# SensorBreakout.net
KiCad netlist of a schematic drawn in Altium Designer
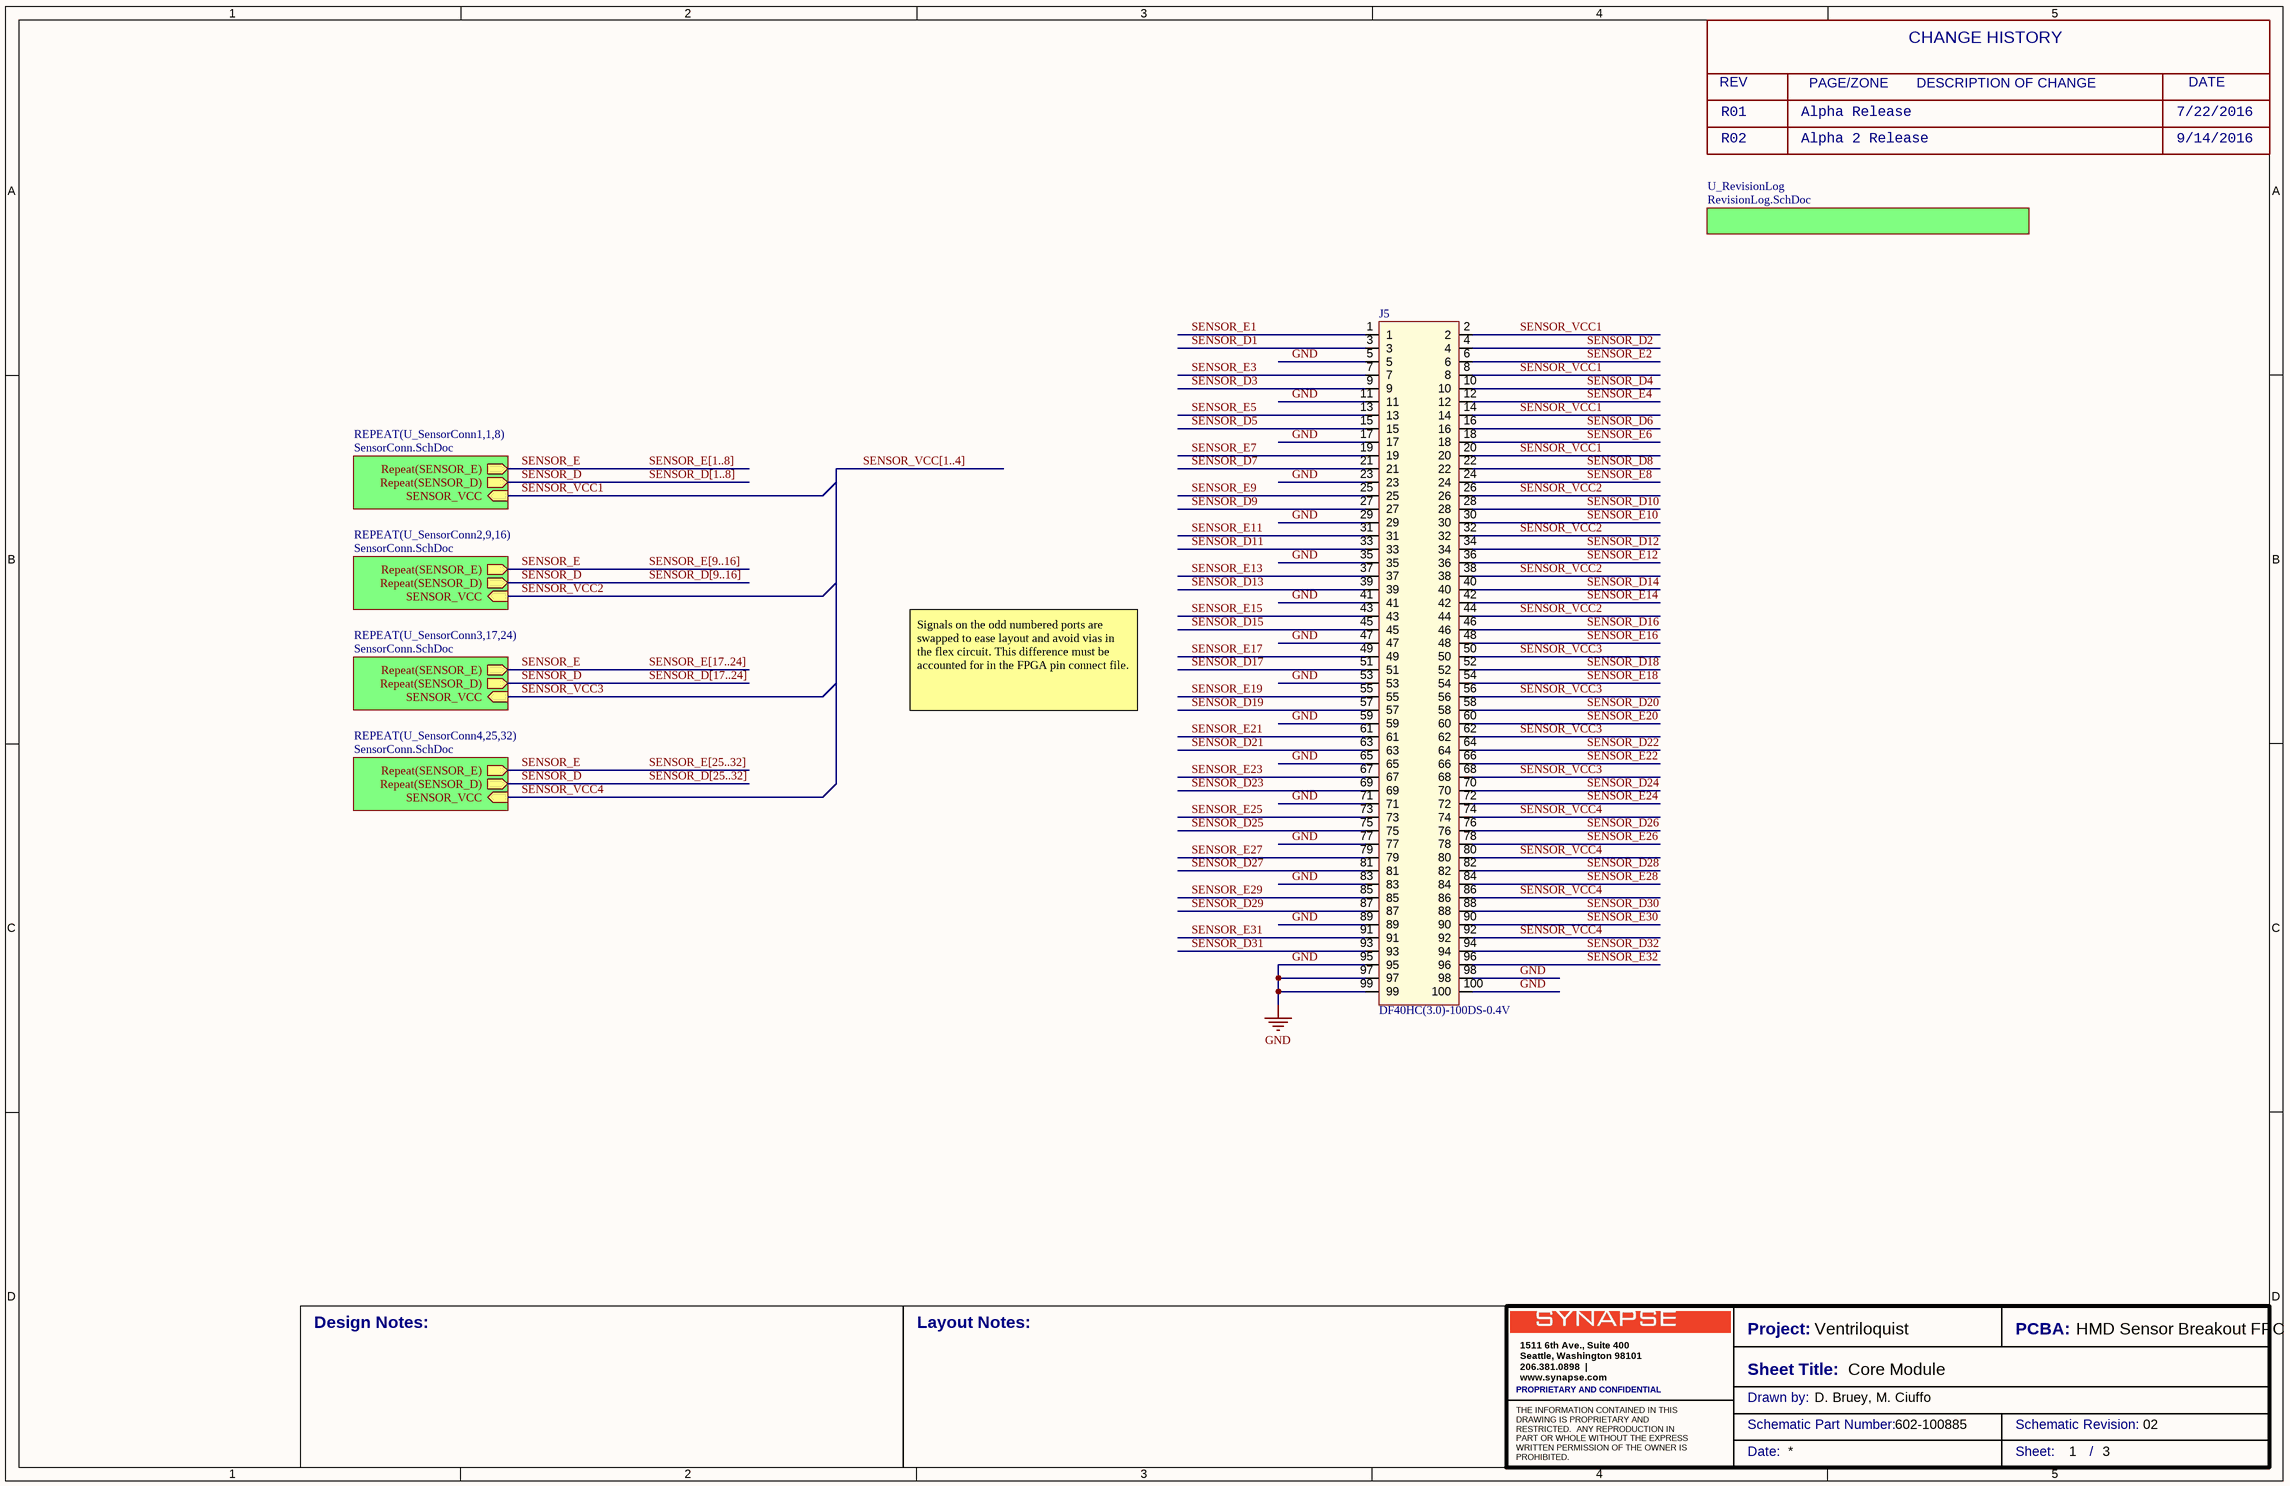
[diagram p0: SensorBreakout.SchDoc]

(export (version "E")
  (design (tool "Eeschema 10.0.6"))
  (components
    (comp (ref "J5")
      (value "DF40HC(3.0)-100DS-0.4V")
      (footprint "con100_hirose-df40c-100ds_129h")
      (description "CONN RCPT 100POS 0.4MM SMD GOLD 3.0MM")
      (fields (field (name "MFG") "Hirose") (field (name "VOLTAGE") "30V"))
      (libsource (lib "SynapseLibrary") (part "DF40C-100DS-0.4(51)"))
    )
  )
  (nets
    (net (code "2") (name "/SENSOR_D1") (class "Default")
      (node (ref "J5") (pin "3") (pinfunction "3_3") (pintype "passive"))
    )
    (net (code "3") (name "/SENSOR_D2") (class "Default")
      (node (ref "J5") (pin "4") (pinfunction "4_4") (pintype "passive"))
    )
    (net (code "4") (name "/SENSOR_D3") (class "Default")
      (node (ref "J5") (pin "9") (pinfunction "9_9") (pintype "passive"))
    )
    (net (code "5") (name "/SENSOR_D4") (class "Default")
      (node (ref "J5") (pin "10") (pinfunction "10_10") (pintype "passive"))
    )
    (net (code "6") (name "/SENSOR_D5") (class "Default")
      (node (ref "J5") (pin "15") (pinfunction "15_15") (pintype "passive"))
    )
    (net (code "7") (name "/SENSOR_D6") (class "Default")
      (node (ref "J5") (pin "16") (pinfunction "16_16") (pintype "passive"))
    )
    (net (code "8") (name "/SENSOR_D7") (class "Default")
      (node (ref "J5") (pin "21") (pinfunction "21_21") (pintype "passive"))
    )
    (net (code "9") (name "/SENSOR_D8") (class "Default")
      (node (ref "J5") (pin "22") (pinfunction "22_22") (pintype "passive"))
    )
    (net (code "10") (name "/SENSOR_D9") (class "Default")
      (node (ref "J5") (pin "27") (pinfunction "27_27") (pintype "passive"))
    )
    (net (code "11") (name "/SENSOR_D10") (class "Default")
      (node (ref "J5") (pin "28") (pinfunction "28_28") (pintype "passive"))
    )
    (net (code "12") (name "/SENSOR_D11") (class "Default")
      (node (ref "J5") (pin "33") (pinfunction "33_33") (pintype "passive"))
    )
    (net (code "13") (name "/SENSOR_D12") (class "Default")
      (node (ref "J5") (pin "34") (pinfunction "34_34") (pintype "passive"))
    )
    (net (code "14") (name "/SENSOR_D13") (class "Default")
      (node (ref "J5") (pin "39") (pinfunction "39_39") (pintype "passive"))
    )
    (net (code "15") (name "/SENSOR_D14") (class "Default")
      (node (ref "J5") (pin "40") (pinfunction "40_40") (pintype "passive"))
    )
    (net (code "16") (name "/SENSOR_D15") (class "Default")
      (node (ref "J5") (pin "45") (pinfunction "45_45") (pintype "passive"))
    )
    (net (code "17") (name "/SENSOR_D16") (class "Default")
      (node (ref "J5") (pin "46") (pinfunction "46_46") (pintype "passive"))
    )
    (net (code "18") (name "/SENSOR_D17") (class "Default")
      (node (ref "J5") (pin "51") (pinfunction "51_51") (pintype "passive"))
    )
    (net (code "19") (name "/SENSOR_D18") (class "Default")
      (node (ref "J5") (pin "52") (pinfunction "52_52") (pintype "passive"))
    )
    (net (code "20") (name "/SENSOR_D19") (class "Default")
      (node (ref "J5") (pin "57") (pinfunction "57_57") (pintype "passive"))
    )
    (net (code "21") (name "/SENSOR_D20") (class "Default")
      (node (ref "J5") (pin "58") (pinfunction "58_58") (pintype "passive"))
    )
    (net (code "22") (name "/SENSOR_D21") (class "Default")
      (node (ref "J5") (pin "63") (pinfunction "63_63") (pintype "passive"))
    )
    (net (code "23") (name "/SENSOR_D22") (class "Default")
      (node (ref "J5") (pin "64") (pinfunction "64_64") (pintype "passive"))
    )
    (net (code "24") (name "/SENSOR_D23") (class "Default")
      (node (ref "J5") (pin "69") (pinfunction "69_69") (pintype "passive"))
    )
    (net (code "25") (name "/SENSOR_D24") (class "Default")
      (node (ref "J5") (pin "70") (pinfunction "70_70") (pintype "passive"))
    )
    (net (code "26") (name "/SENSOR_D25") (class "Default")
      (node (ref "J5") (pin "75") (pinfunction "75_75") (pintype "passive"))
    )
    (net (code "27") (name "/SENSOR_D26") (class "Default")
      (node (ref "J5") (pin "76") (pinfunction "76_76") (pintype "passive"))
    )
    (net (code "28") (name "/SENSOR_D27") (class "Default")
      (node (ref "J5") (pin "81") (pinfunction "81_81") (pintype "passive"))
    )
    (net (code "29") (name "/SENSOR_D28") (class "Default")
      (node (ref "J5") (pin "82") (pinfunction "82_82") (pintype "passive"))
    )
    (net (code "30") (name "/SENSOR_D29") (class "Default")
      (node (ref "J5") (pin "87") (pinfunction "87_87") (pintype "passive"))
    )
    (net (code "31") (name "/SENSOR_D30") (class "Default")
      (node (ref "J5") (pin "88") (pinfunction "88_88") (pintype "passive"))
    )
    (net (code "32") (name "/SENSOR_D31") (class "Default")
      (node (ref "J5") (pin "93") (pinfunction "93_93") (pintype "passive"))
    )
    (net (code "33") (name "/SENSOR_D32") (class "Default")
      (node (ref "J5") (pin "94") (pinfunction "94_94") (pintype "passive"))
    )
    (net (code "39") (name "/SENSOR_E1") (class "Default")
      (node (ref "J5") (pin "1") (pinfunction "1_1") (pintype "passive"))
    )
    (net (code "40") (name "/SENSOR_E2") (class "Default")
      (node (ref "J5") (pin "6") (pinfunction "6_6") (pintype "passive"))
    )
    (net (code "41") (name "/SENSOR_E3") (class "Default")
      (node (ref "J5") (pin "7") (pinfunction "7_7") (pintype "passive"))
    )
    (net (code "42") (name "/SENSOR_E4") (class "Default")
      (node (ref "J5") (pin "12") (pinfunction "12_12") (pintype "passive"))
    )
    (net (code "43") (name "/SENSOR_E5") (class "Default")
      (node (ref "J5") (pin "13") (pinfunction "13_13") (pintype "passive"))
    )
    (net (code "44") (name "/SENSOR_E6") (class "Default")
      (node (ref "J5") (pin "18") (pinfunction "18_18") (pintype "passive"))
    )
    (net (code "45") (name "/SENSOR_E7") (class "Default")
      (node (ref "J5") (pin "19") (pinfunction "19_19") (pintype "passive"))
    )
    (net (code "46") (name "/SENSOR_E8") (class "Default")
      (node (ref "J5") (pin "24") (pinfunction "24_24") (pintype "passive"))
    )
    (net (code "47") (name "/SENSOR_E9") (class "Default")
      (node (ref "J5") (pin "25") (pinfunction "25_25") (pintype "passive"))
    )
    (net (code "48") (name "/SENSOR_E10") (class "Default")
      (node (ref "J5") (pin "30") (pinfunction "30_30") (pintype "passive"))
    )
    (net (code "49") (name "/SENSOR_E11") (class "Default")
      (node (ref "J5") (pin "31") (pinfunction "31_31") (pintype "passive"))
    )
    (net (code "50") (name "/SENSOR_E12") (class "Default")
      (node (ref "J5") (pin "36") (pinfunction "36_36") (pintype "passive"))
    )
    (net (code "51") (name "/SENSOR_E13") (class "Default")
      (node (ref "J5") (pin "37") (pinfunction "37_37") (pintype "passive"))
    )
    (net (code "52") (name "/SENSOR_E14") (class "Default")
      (node (ref "J5") (pin "42") (pinfunction "42_42") (pintype "passive"))
    )
    (net (code "53") (name "/SENSOR_E15") (class "Default")
      (node (ref "J5") (pin "43") (pinfunction "43_43") (pintype "passive"))
    )
    (net (code "54") (name "/SENSOR_E16") (class "Default")
      (node (ref "J5") (pin "48") (pinfunction "48_48") (pintype "passive"))
    )
    (net (code "55") (name "/SENSOR_E17") (class "Default")
      (node (ref "J5") (pin "49") (pinfunction "49_49") (pintype "passive"))
    )
    (net (code "56") (name "/SENSOR_E18") (class "Default")
      (node (ref "J5") (pin "54") (pinfunction "54_54") (pintype "passive"))
    )
    (net (code "57") (name "/SENSOR_E19") (class "Default")
      (node (ref "J5") (pin "55") (pinfunction "55_55") (pintype "passive"))
    )
    (net (code "58") (name "/SENSOR_E20") (class "Default")
      (node (ref "J5") (pin "60") (pinfunction "60_60") (pintype "passive"))
    )
    (net (code "59") (name "/SENSOR_E21") (class "Default")
      (node (ref "J5") (pin "61") (pinfunction "61_61") (pintype "passive"))
    )
    (net (code "60") (name "/SENSOR_E22") (class "Default")
      (node (ref "J5") (pin "66") (pinfunction "66_66") (pintype "passive"))
    )
    (net (code "61") (name "/SENSOR_E23") (class "Default")
      (node (ref "J5") (pin "67") (pinfunction "67_67") (pintype "passive"))
    )
    (net (code "62") (name "/SENSOR_E24") (class "Default")
      (node (ref "J5") (pin "72") (pinfunction "72_72") (pintype "passive"))
    )
    (net (code "63") (name "/SENSOR_E25") (class "Default")
      (node (ref "J5") (pin "73") (pinfunction "73_73") (pintype "passive"))
    )
    (net (code "64") (name "/SENSOR_E26") (class "Default")
      (node (ref "J5") (pin "78") (pinfunction "78_78") (pintype "passive"))
    )
    (net (code "65") (name "/SENSOR_E27") (class "Default")
      (node (ref "J5") (pin "79") (pinfunction "79_79") (pintype "passive"))
    )
    (net (code "66") (name "/SENSOR_E28") (class "Default")
      (node (ref "J5") (pin "84") (pinfunction "84_84") (pintype "passive"))
    )
    (net (code "67") (name "/SENSOR_E29") (class "Default")
      (node (ref "J5") (pin "85") (pinfunction "85_85") (pintype "passive"))
    )
    (net (code "68") (name "/SENSOR_E30") (class "Default")
      (node (ref "J5") (pin "90") (pinfunction "90_90") (pintype "passive"))
    )
    (net (code "69") (name "/SENSOR_E31") (class "Default")
      (node (ref "J5") (pin "91") (pinfunction "91_91") (pintype "passive"))
    )
    (net (code "70") (name "/SENSOR_E32") (class "Default")
      (node (ref "J5") (pin "96") (pinfunction "96_96") (pintype "passive"))
    )
    (net (code "75") (name "/SENSOR_VCC1") (class "Default")
      (node (ref "J5") (pin "14") (pinfunction "14_14") (pintype "passive"))
      (node (ref "J5") (pin "2") (pinfunction "2_2") (pintype "passive"))
      (node (ref "J5") (pin "20") (pinfunction "20_20") (pintype "passive"))
      (node (ref "J5") (pin "8") (pinfunction "8_8") (pintype "passive"))
    )
    (net (code "76") (name "/SENSOR_VCC2") (class "Default")
      (node (ref "J5") (pin "26") (pinfunction "26_26") (pintype "passive"))
      (node (ref "J5") (pin "32") (pinfunction "32_32") (pintype "passive"))
      (node (ref "J5") (pin "38") (pinfunction "38_38") (pintype "passive"))
      (node (ref "J5") (pin "44") (pinfunction "44_44") (pintype "passive"))
    )
    (net (code "77") (name "/SENSOR_VCC3") (class "Default")
      (node (ref "J5") (pin "50") (pinfunction "50_50") (pintype "passive"))
      (node (ref "J5") (pin "56") (pinfunction "56_56") (pintype "passive"))
      (node (ref "J5") (pin "62") (pinfunction "62_62") (pintype "passive"))
      (node (ref "J5") (pin "68") (pinfunction "68_68") (pintype "passive"))
    )
    (net (code "78") (name "/SENSOR_VCC4") (class "Default")
      (node (ref "J5") (pin "74") (pinfunction "74_74") (pintype "passive"))
      (node (ref "J5") (pin "80") (pinfunction "80_80") (pintype "passive"))
      (node (ref "J5") (pin "86") (pinfunction "86_86") (pintype "passive"))
      (node (ref "J5") (pin "92") (pinfunction "92_92") (pintype "passive"))
    )
    (net (code "80") (name "GND") (class "Default")
      (node (ref "J5") (pin "100") (pinfunction "100_100") (pintype "passive"))
      (node (ref "J5") (pin "11") (pinfunction "11_11") (pintype "passive"))
      (node (ref "J5") (pin "17") (pinfunction "17_17") (pintype "passive"))
      (node (ref "J5") (pin "23") (pinfunction "23_23") (pintype "passive"))
      (node (ref "J5") (pin "29") (pinfunction "29_29") (pintype "passive"))
      (node (ref "J5") (pin "35") (pinfunction "35_35") (pintype "passive"))
      (node (ref "J5") (pin "41") (pinfunction "41_41") (pintype "passive"))
      (node (ref "J5") (pin "47") (pinfunction "47_47") (pintype "passive"))
      (node (ref "J5") (pin "5") (pinfunction "5_5") (pintype "passive"))
      (node (ref "J5") (pin "53") (pinfunction "53_53") (pintype "passive"))
      (node (ref "J5") (pin "59") (pinfunction "59_59") (pintype "passive"))
      (node (ref "J5") (pin "65") (pinfunction "65_65") (pintype "passive"))
      (node (ref "J5") (pin "71") (pinfunction "71_71") (pintype "passive"))
      (node (ref "J5") (pin "77") (pinfunction "77_77") (pintype "passive"))
      (node (ref "J5") (pin "83") (pinfunction "83_83") (pintype "passive"))
      (node (ref "J5") (pin "89") (pinfunction "89_89") (pintype "passive"))
      (node (ref "J5") (pin "95") (pinfunction "95_95") (pintype "passive"))
      (node (ref "J5") (pin "97") (pinfunction "97_97") (pintype "passive"))
      (node (ref "J5") (pin "98") (pinfunction "98_98") (pintype "passive"))
      (node (ref "J5") (pin "99") (pinfunction "99_99") (pintype "passive"))
    )
  )
)
